# DCDC_CHANNEL.net
KiCad netlist of a schematic drawn in Altium Designer
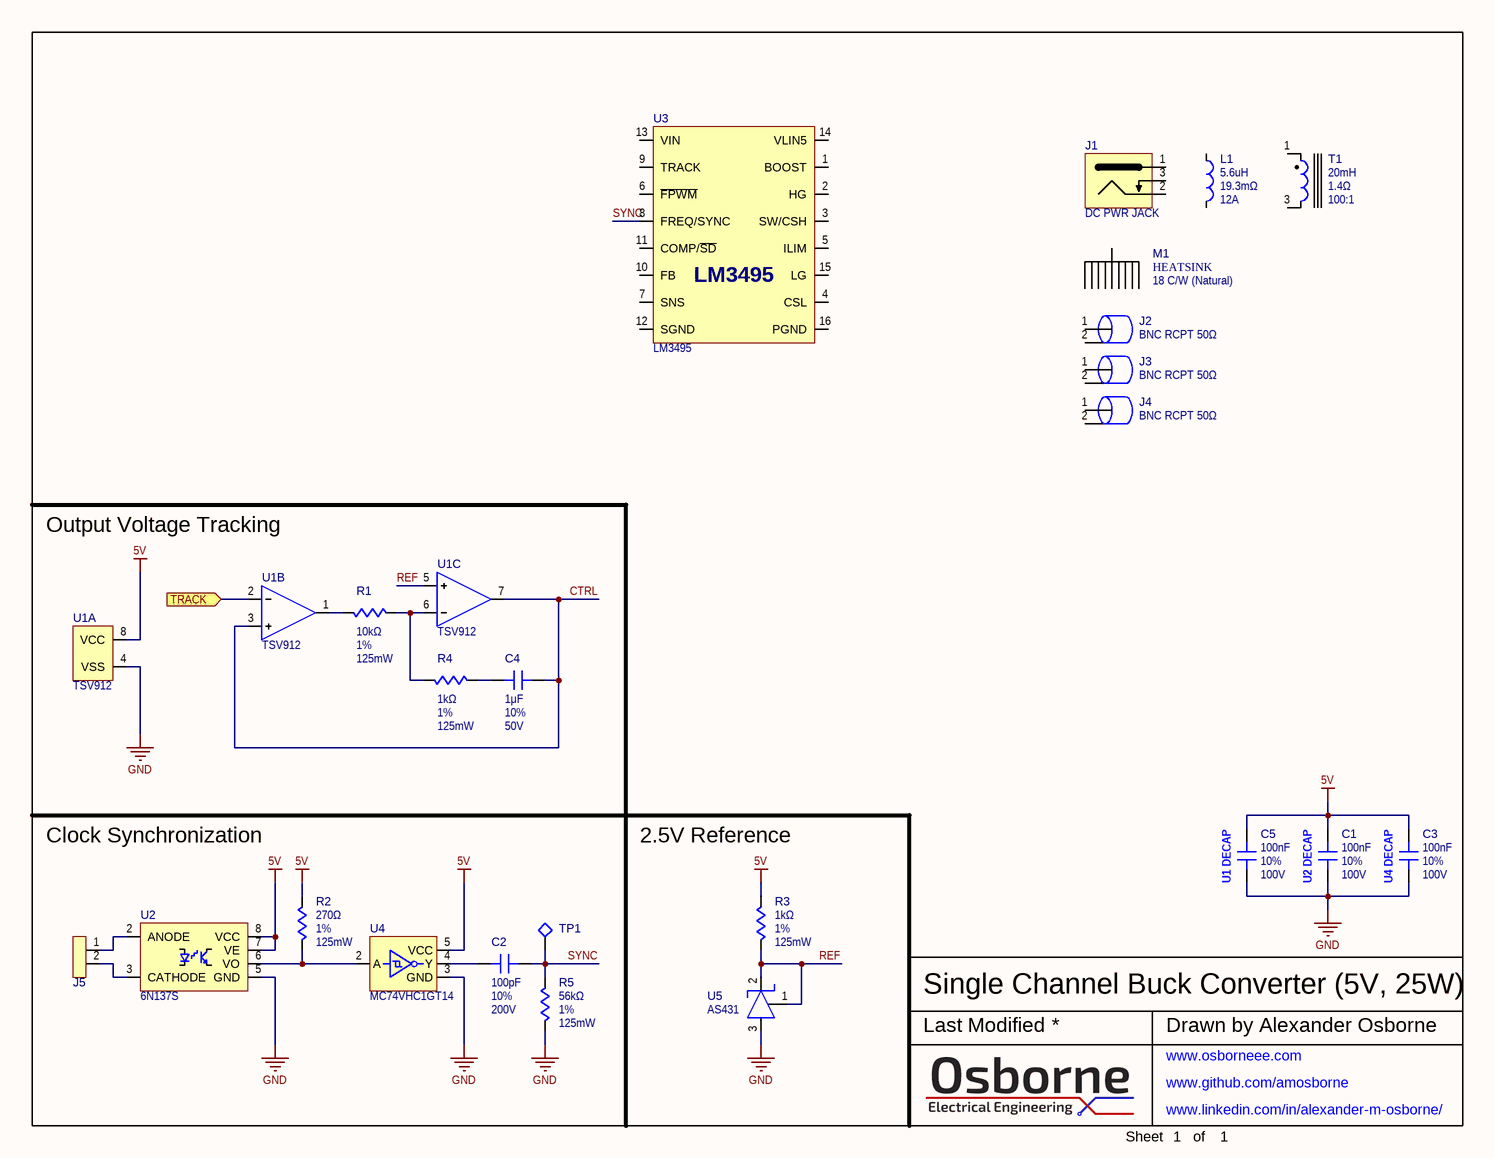
[diagram p0: DCDC_CHANNEL.SchDoc]

(export (version "E")
  (design (tool "Eeschema 10.0.6"))
  (components
    (comp (ref "C1")
      (value "100nF")
      (description "CAP, CER, 100nF ±10%, 100V, 0805")
      (fields
        (field (name "VOLTAGE") "100V")
        (field (name "TOLERANCE") "10%")
        (field (name "Comment") "732-12244-1-ND")
      )
      (libsource (lib "DCDC_CHANNEL") (part "CAP-CER-100N-10T-100V-0805"))
    )
    (comp (ref "C2")
      (value "100pF")
      (description "CAP, CER, 100pF ±10%, 200V, 0805")
      (fields
        (field (name "VOLTAGE") "200V")
        (field (name "TOLERANCE") "10%")
        (field (name "Comment") "732-12161-1-ND")
      )
      (libsource (lib "DCDC_CHANNEL") (part "CAP-CER-100P-10T-200V-0805"))
    )
    (comp (ref "C3")
      (value "100nF")
      (description "CAP, CER, 100nF ±10%, 100V, 0805")
      (fields
        (field (name "VOLTAGE") "100V")
        (field (name "TOLERANCE") "10%")
        (field (name "Comment") "732-12244-1-ND")
      )
      (libsource (lib "DCDC_CHANNEL") (part "CAP-CER-100N-10T-100V-0805"))
    )
    (comp (ref "C4")
      (value "1μF")
      (description "CAP, CER, 1μF ±10%, 50V, 0805")
      (fields
        (field (name "VOLTAGE") "50V")
        (field (name "TOLERANCE") "10%")
        (field (name "Comment") "1276-2928-1-ND")
      )
      (libsource (lib "DCDC_CHANNEL") (part "CAP-CER-1U00-10T-50V-0805"))
    )
    (comp (ref "C5")
      (value "100nF")
      (description "CAP, CER, 100nF ±10%, 100V, 0805")
      (fields
        (field (name "VOLTAGE") "100V")
        (field (name "TOLERANCE") "10%")
        (field (name "Comment") "732-12244-1-ND")
      )
      (libsource (lib "DCDC_CHANNEL") (part "CAP-CER-100N-10T-100V-0805"))
    )
    (comp (ref "J1")
      (value "DC PWR JACK")
      (description "DC Power Jack, 48V, 6.5A")
      (libsource (lib "DCDC_CHANNEL") (part "DC-PWR-JACK"))
    )
    (comp (ref "J2")
      (value "BNC RCPT 50Ω")
      (description "BNC Receptacle, 50Ω")
      (libsource (lib "DCDC_CHANNEL") (part "BNC-RCPT"))
    )
    (comp (ref "J3")
      (value "BNC RCPT 50Ω")
      (description "BNC Receptacle, 50Ω")
      (libsource (lib "DCDC_CHANNEL") (part "BNC-RCPT"))
    )
    (comp (ref "J4")
      (value "BNC RCPT 50Ω")
      (description "BNC Receptacle, 50Ω")
      (libsource (lib "DCDC_CHANNEL") (part "BNC-RCPT"))
    )
    (comp (ref "J5")
      (value "~")
      (description "Header 1x2 THT")
      (libsource (lib "DCDC_CHANNEL") (part "HEADER_1x2"))
    )
    (comp (ref "L1")
      (value "5.6uH")
      (description "IND, 5.6uH ±20.0%, 19.3mΩ DCR, 12A Irms")
      (fields
        (field (name "IRMS") "12A")
        (field (name "DCR") "19.3mΩ")
        (field (name "Comment") "SRP1038C-5R6MCT-ND")
      )
      (libsource (lib "DCDC_CHANNEL") (part "IND-5U60-20T0-12A0"))
    )
    (comp (ref "M1")
      (value "HEATSINK")
      (description "Heatsink, 18C/W @ Natural")
      (fields (field (name "THETA") "18 C/W (Natural)"))
      (libsource (lib "DCDC_CHANNEL") (part "HEATSINK"))
    )
    (comp (ref "R1")
      (value "10kΩ")
      (description "RES, 10kΩ ±1.00%, 125mW, 0805")
      (fields
        (field (name "TOLERANCE") "1%")
        (field (name "POWER") "125mW")
        (field (name "Comment") "RMCF0805FT10K0CT-ND")
      )
      (libsource (lib "DCDC_CHANNEL") (part "RES-10K0-1T00-W125-0805"))
    )
    (comp (ref "R2")
      (value "270Ω")
      (description "RES, 270Ω ±1.00%, 125mW, 0805")
      (fields
        (field (name "TOLERANCE") "1%")
        (field (name "POWER") "125mW")
        (field (name "Comment") "RMCF0805FT270RCT-ND")
      )
      (libsource (lib "DCDC_CHANNEL") (part "RES-270R-1T00-W125-0805"))
    )
    (comp (ref "R3")
      (value "1kΩ")
      (description "RES, 1kΩ ±1.00%, 125mW, 0805")
      (fields
        (field (name "TOLERANCE") "1%")
        (field (name "POWER") "125mW")
        (field (name "Comment") "RMCF0805FT1K00CT-ND")
      )
      (libsource (lib "DCDC_CHANNEL") (part "RES-1K00-1T00-W125-0805"))
    )
    (comp (ref "R4")
      (value "1kΩ")
      (description "RES, 1kΩ ±1.00%, 125mW, 0805")
      (fields
        (field (name "TOLERANCE") "1%")
        (field (name "POWER") "125mW")
        (field (name "Comment") "RMCF0805FT1K00CT-ND")
      )
      (libsource (lib "DCDC_CHANNEL") (part "RES-1K00-1T00-W125-0805"))
    )
    (comp (ref "R5")
      (value "56kΩ")
      (description "RES, 56kΩ ±1.00%, 125mW, 0805")
      (fields
        (field (name "TOLERANCE") "1%")
        (field (name "POWER") "125mW")
        (field (name "Comment") "RMCF0805FT56K0CT-ND")
      )
      (libsource (lib "DCDC_CHANNEL") (part "RES-56K0-1T00-W125-0805"))
    )
    (comp (ref "T1")
      (value "20mH")
      (description "XFMR, 20mH, 1.4Ω DCR, 100:1")
      (fields (field (name "N") "100:1") (field (name "DCR") "1.4Ω") (field (name "Comment") "553-1543-ND"))
      (libsource (lib "DCDC_CHANNEL") (part "XFMR-20M0-100N"))
    )
    (comp (ref "TP1")
      (value "36-1033-ND")
      (description "Test Point Loop")
      (libsource (lib "DCDC_CHANNEL") (part "TEST-POINT"))
    )
    (comp (ref "U1")
      (value "TSV912")
      (description "Operational Amplifier, Rail-to-Rail")
      (libsource (lib "") (part "TSV912_1"))
    )
    (comp (ref "U2")
      (value "6N137S")
      (description "High-Speed Optocoupler, 10MBd")
      (libsource (lib "DCDC_CHANNEL") (part "6N137S"))
    )
    (comp (ref "U3")
      (value "LM3495")
      (description "Current Mode Buck Controller")
      (libsource (lib "DCDC_CHANNEL") (part "LM3495"))
    )
    (comp (ref "U4")
      (value "MC74VHC1GT14")
      (description "Schmitt Trigger Inverter, TTL")
      (libsource (lib "DCDC_CHANNEL") (part "MC74VHC1GT14"))
    )
    (comp (ref "U5")
      (value "AS431")
      (description "Shunt Voltage Reference, 2.5V, 0.5%")
      (libsource (lib "DCDC_CHANNEL") (part "AS431"))
    )
  )
  (nets
    (net (code "1") (name "/CTRL") (class "Default")
      (node (ref "C4") (pin "1") (pintype "passive"))
      (node (ref "U1") (pin "3") (pinfunction "+IN_A_3") (pintype "passive"))
      (node (ref "U1") (pin "7") (pinfunction "OUT_B_7") (pintype "passive"))
    )
    (net (code "2") (name "/REF") (class "Default")
      (node (ref "R3") (pin "2") (pintype "passive"))
      (node (ref "U1") (pin "5") (pinfunction "+IN_B_5") (pintype "passive"))
      (node (ref "U5") (pin "1") (pinfunction "REF_1") (pintype "passive"))
      (node (ref "U5") (pin "2") (pinfunction "CATHODE_2") (pintype "passive"))
    )
    (net (code "3") (name "/SYNC") (class "Default")
      (node (ref "C2") (pin "2") (pintype "passive"))
      (node (ref "R5") (pin "1") (pintype "passive"))
      (node (ref "TP1") (pin "1") (pinfunction "12_1") (pintype "passive"))
      (node (ref "U3") (pin "8") (pinfunction "FREQ/SYNC_8") (pintype "passive"))
    )
    (net (code "4") (name "/TRACK") (class "Default")
      (node (ref "U1") (pin "2") (pinfunction "-IN_A_2") (pintype "passive"))
    )
    (net (code "5") (name "5V") (class "Default")
      (node (ref "C1") (pin "1") (pintype "passive"))
      (node (ref "C3") (pin "1") (pintype "passive"))
      (node (ref "C5") (pin "1") (pintype "passive"))
      (node (ref "R2") (pin "1") (pintype "passive"))
      (node (ref "R3") (pin "1") (pintype "passive"))
      (node (ref "U1") (pin "8") (pinfunction "VCC_8") (pintype "passive"))
      (node (ref "U2") (pin "7") (pinfunction "VE_7") (pintype "passive"))
      (node (ref "U2") (pin "8") (pinfunction "VCC_8") (pintype "power_in"))
      (node (ref "U4") (pin "5") (pinfunction "VCC_5") (pintype "passive"))
    )
    (net (code "6") (name "GND") (class "Default")
      (node (ref "C1") (pin "2") (pintype "passive"))
      (node (ref "C3") (pin "2") (pintype "passive"))
      (node (ref "C5") (pin "2") (pintype "passive"))
      (node (ref "R5") (pin "2") (pintype "passive"))
      (node (ref "U1") (pin "4") (pinfunction "VSS_4") (pintype "passive"))
      (node (ref "U2") (pin "5") (pinfunction "GND_5") (pintype "power_in"))
      (node (ref "U4") (pin "3") (pinfunction "GND_3") (pintype "passive"))
      (node (ref "U5") (pin "3") (pinfunction "ANODE_3") (pintype "passive"))
    )
    (net (code "7") (name "Net-(C4-Pad2)") (class "Default")
      (node (ref "C4") (pin "2") (pintype "passive"))
      (node (ref "R4") (pin "2") (pintype "passive"))
    )
    (net (code "8") (name "Net-(U1B-OUT_A)") (class "Default")
      (node (ref "R1") (pin "1") (pintype "passive"))
      (node (ref "U1") (pin "1") (pinfunction "OUT_A_1") (pintype "passive"))
    )
    (net (code "9") (name "Net-(U1C--IN_B)") (class "Default")
      (node (ref "R1") (pin "2") (pintype "passive"))
      (node (ref "R4") (pin "1") (pintype "passive"))
      (node (ref "U1") (pin "6") (pinfunction "-IN_B_6") (pintype "passive"))
    )
    (net (code "10") (name "Net-(U2-ANODE)") (class "Default")
      (node (ref "J5") (pin "1") (pinfunction "12_1") (pintype "passive"))
      (node (ref "U2") (pin "2") (pinfunction "ANODE_2") (pintype "passive"))
    )
    (net (code "11") (name "Net-(U2-CATHODE)") (class "Default")
      (node (ref "J5") (pin "2") (pinfunction "12_2") (pintype "passive"))
      (node (ref "U2") (pin "3") (pinfunction "CATHODE_3") (pintype "passive"))
    )
    (net (code "12") (name "Net-(U2-VO)") (class "Default")
      (node (ref "R2") (pin "2") (pintype "passive"))
      (node (ref "U2") (pin "6") (pinfunction "VO_6") (pintype "open_collector"))
      (node (ref "U4") (pin "2") (pinfunction "A_2") (pintype "passive"))
    )
    (net (code "13") (name "Net-(U4-Y)") (class "Default")
      (node (ref "C2") (pin "1") (pintype "passive"))
      (node (ref "U4") (pin "4") (pinfunction "Y_4") (pintype "passive"))
    )
    (net (code "14") (name "unconnected-(J1-9-Pad1)") (class "Default")
      (node (ref "J1") (pin "1") (pinfunction "9_1") (pintype "passive"))
    )
    (net (code "15") (name "unconnected-(J1-10-Pad3)") (class "Default")
      (node (ref "J1") (pin "3") (pinfunction "10_3") (pintype "passive"))
    )
    (net (code "16") (name "unconnected-(J1-11-Pad2)") (class "Default")
      (node (ref "J1") (pin "2") (pinfunction "11_2") (pintype "passive"))
    )
    (net (code "17") (name "unconnected-(J2-12-Pad1)") (class "Default")
      (node (ref "J2") (pin "1") (pinfunction "12_1") (pintype "passive"))
    )
    (net (code "18") (name "unconnected-(J2-12-Pad2)") (class "Default")
      (node (ref "J2") (pin "2") (pinfunction "12_2") (pintype "passive"))
    )
    (net (code "19") (name "unconnected-(J3-12-Pad1)") (class "Default")
      (node (ref "J3") (pin "1") (pinfunction "12_1") (pintype "passive"))
    )
    (net (code "20") (name "unconnected-(J3-12-Pad2)") (class "Default")
      (node (ref "J3") (pin "2") (pinfunction "12_2") (pintype "passive"))
    )
    (net (code "21") (name "unconnected-(J4-12-Pad1)") (class "Default")
      (node (ref "J4") (pin "1") (pinfunction "12_1") (pintype "passive"))
    )
    (net (code "22") (name "unconnected-(J4-12-Pad2)") (class "Default")
      (node (ref "J4") (pin "2") (pinfunction "12_2") (pintype "passive"))
    )
    (net (code "23") (name "unconnected-(L1-Pad1)") (class "Default")
      (node (ref "L1") (pin "1") (pintype "passive"))
    )
    (net (code "24") (name "unconnected-(L1-Pad2)") (class "Default")
      (node (ref "L1") (pin "2") (pintype "passive"))
    )
    (net (code "25") (name "unconnected-(M1-8-Pad1)") (class "Default")
      (node (ref "M1") (pin "1") (pinfunction "8_1") (pintype "passive"))
    )
    (net (code "26") (name "unconnected-(T1-Pad1)") (class "Default")
      (node (ref "T1") (pin "1") (pintype "passive"))
    )
    (net (code "27") (name "unconnected-(T1-Pad3)") (class "Default")
      (node (ref "T1") (pin "3") (pintype "passive"))
    )
    (net (code "28") (name "unconnected-(U3-BOOST-Pad1)") (class "Default")
      (node (ref "U3") (pin "1") (pinfunction "BOOST_1") (pintype "passive"))
    )
    (net (code "29") (name "unconnected-(U3-COMP{slash}~{SD}-Pad11)") (class "Default")
      (node (ref "U3") (pin "11") (pinfunction "COMP/~{SD}_11") (pintype "passive"))
    )
    (net (code "30") (name "unconnected-(U3-CSL-Pad4)") (class "Default")
      (node (ref "U3") (pin "4") (pinfunction "CSL_4") (pintype "passive"))
    )
    (net (code "31") (name "unconnected-(U3-FB-Pad10)") (class "Default")
      (node (ref "U3") (pin "10") (pinfunction "FB_10") (pintype "passive"))
    )
    (net (code "32") (name "unconnected-(U3-HG-Pad2)") (class "Default")
      (node (ref "U3") (pin "2") (pinfunction "HG_2") (pintype "passive"))
    )
    (net (code "33") (name "unconnected-(U3-ILIM-Pad5)") (class "Default")
      (node (ref "U3") (pin "5") (pinfunction "ILIM_5") (pintype "passive"))
    )
    (net (code "34") (name "unconnected-(U3-LG-Pad15)") (class "Default")
      (node (ref "U3") (pin "15") (pinfunction "LG_15") (pintype "passive"))
    )
    (net (code "35") (name "unconnected-(U3-PGND-Pad16)") (class "Default")
      (node (ref "U3") (pin "16") (pinfunction "PGND_16") (pintype "power_in"))
    )
    (net (code "36") (name "unconnected-(U3-SGND-Pad12)") (class "Default")
      (node (ref "U3") (pin "12") (pinfunction "SGND_12") (pintype "power_in"))
    )
    (net (code "37") (name "unconnected-(U3-SNS-Pad7)") (class "Default")
      (node (ref "U3") (pin "7") (pinfunction "SNS_7") (pintype "passive"))
    )
    (net (code "38") (name "unconnected-(U3-SW{slash}CSH-Pad3)") (class "Default")
      (node (ref "U3") (pin "3") (pinfunction "SW/CSH_3") (pintype "passive"))
    )
    (net (code "39") (name "unconnected-(U3-TRACK-Pad9)") (class "Default")
      (node (ref "U3") (pin "9") (pinfunction "TRACK_9") (pintype "passive"))
    )
    (net (code "40") (name "unconnected-(U3-VIN-Pad13)") (class "Default")
      (node (ref "U3") (pin "13") (pinfunction "VIN_13") (pintype "power_in"))
    )
    (net (code "41") (name "unconnected-(U3-VLIN5-Pad14)") (class "Default")
      (node (ref "U3") (pin "14") (pinfunction "VLIN5_14") (pintype "passive"))
    )
    (net (code "42") (name "unconnected-(U3-~{FPWM}-Pad6)") (class "Default")
      (node (ref "U3") (pin "6") (pinfunction "~{FPWM}_6") (pintype "passive"))
    )
    (net (code "43") (name "unconnected-(U4-NC-Pad1)") (class "Default")
      (node (ref "U4") (pin "1") (pinfunction "NC_1") (pintype "passive"))
    )
  )
)
